# PiGateway2_2.net
KiCad netlist of a schematic drawn in EAGLE
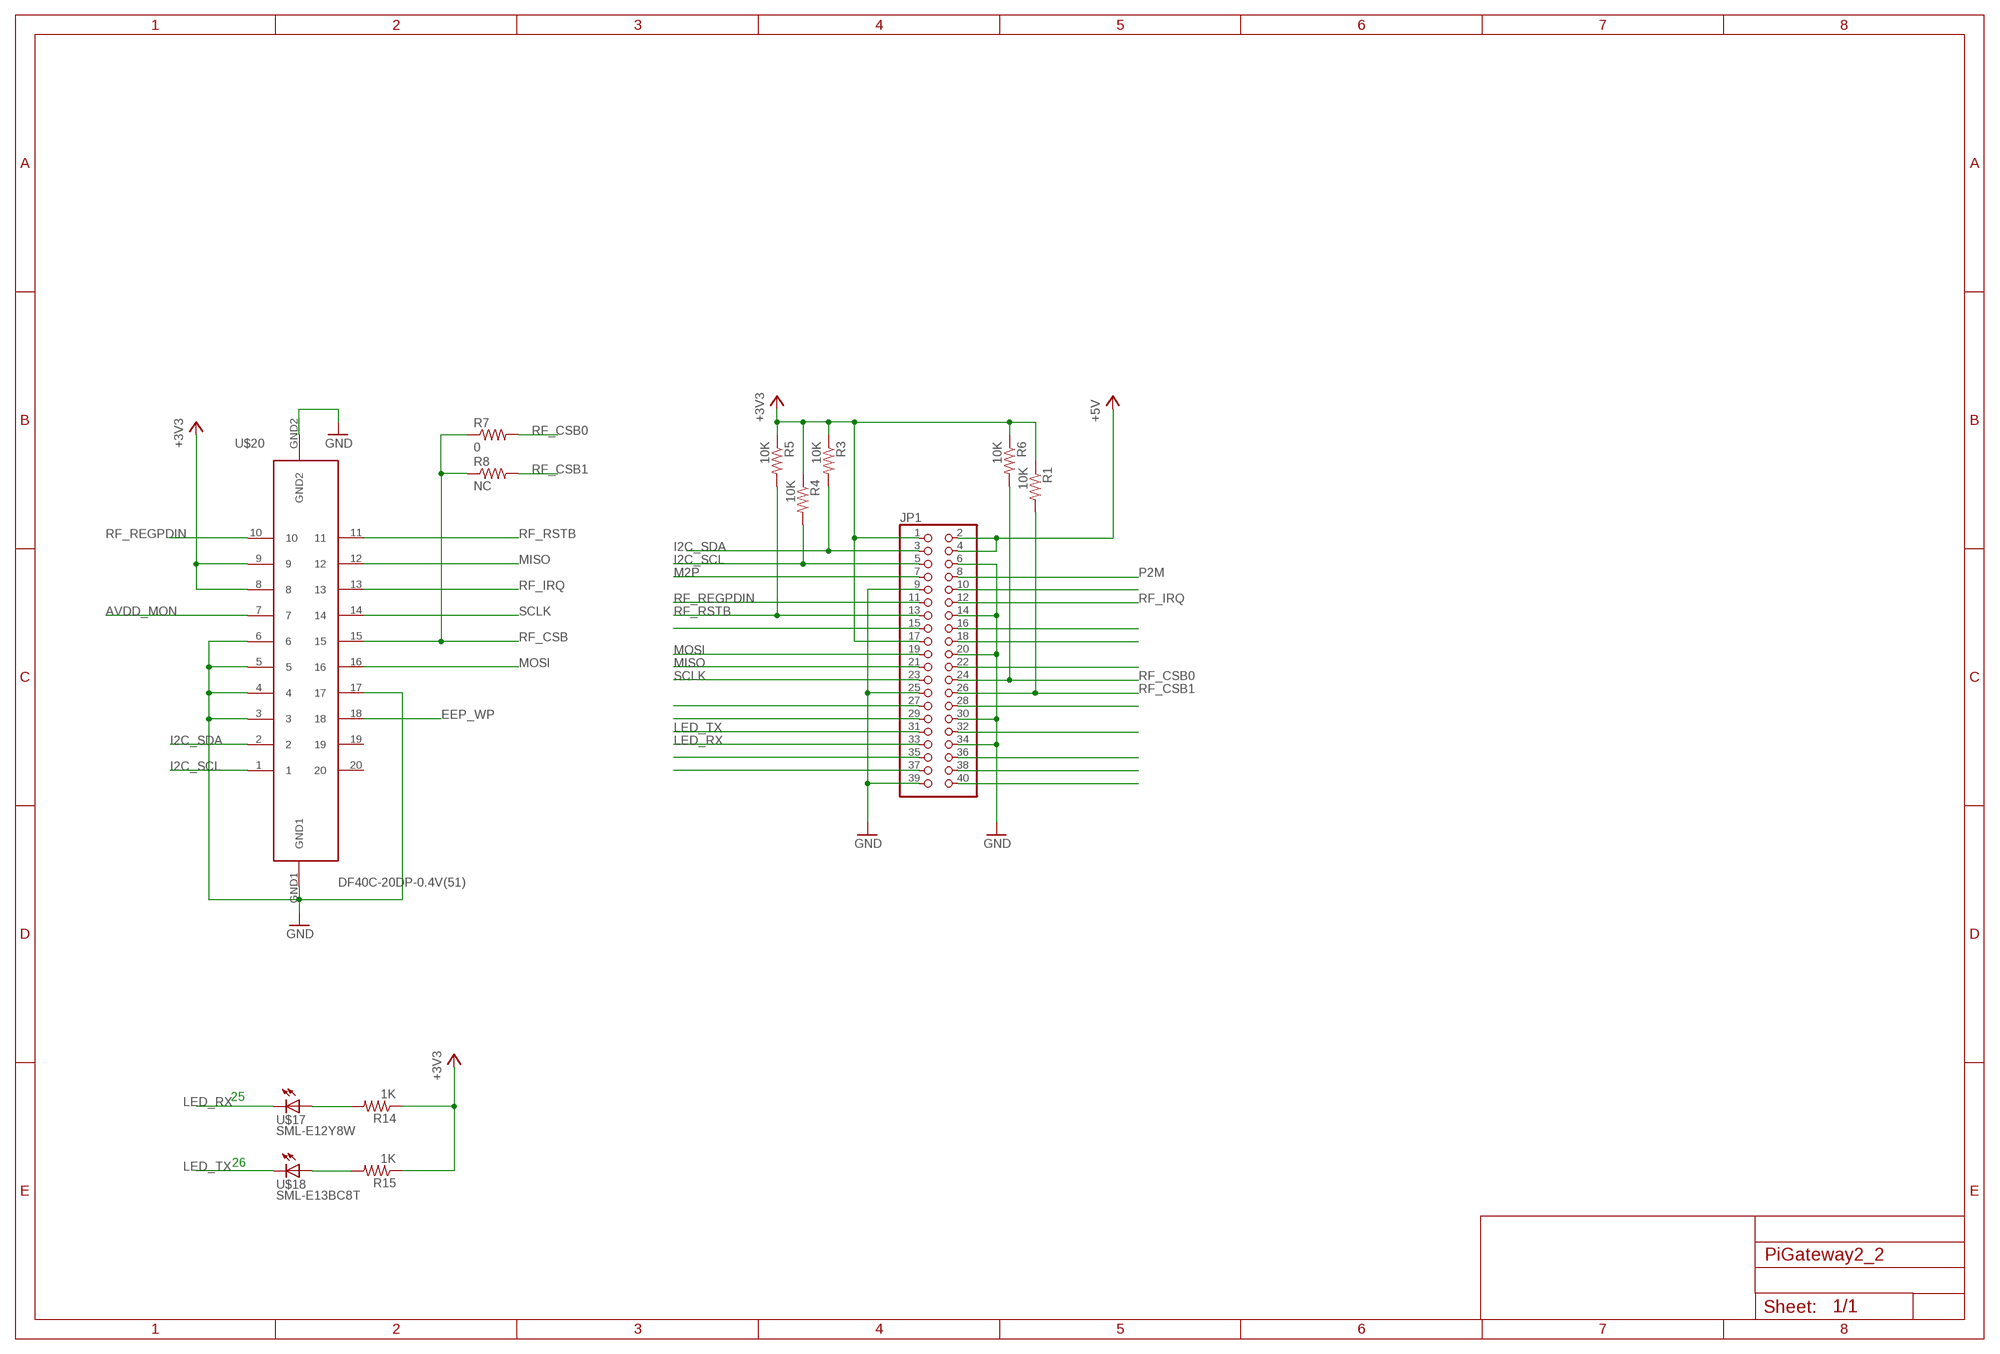
[diagram p0: schematic, sheet 1]

(export (version "E")
  (design (tool "Eeschema 10.0.6"))
  (components
    (comp (ref "JP1")
      (value "PINHD-2X20")
      (footprint "eagle-import:2X20")
      (libsource (lib "eagle-import") (part "PINHD-2X20"))
    )
    (comp (ref "R1")
      (value "10K")
      (footprint "eagle-import:R0402")
      (libsource (lib "eagle-import") (part "R-US_R0402"))
    )
    (comp (ref "R3")
      (value "10K")
      (footprint "eagle-import:R0402")
      (libsource (lib "eagle-import") (part "R-US_R0402"))
    )
    (comp (ref "R4")
      (value "10K")
      (footprint "eagle-import:R0402")
      (libsource (lib "eagle-import") (part "R-US_R0402"))
    )
    (comp (ref "R5")
      (value "10K")
      (footprint "eagle-import:R0402")
      (libsource (lib "eagle-import") (part "R-US_R0402"))
    )
    (comp (ref "R6")
      (value "10K")
      (footprint "eagle-import:R0402")
      (libsource (lib "eagle-import") (part "R-US_R0402"))
    )
    (comp (ref "R7")
      (value "0")
      (footprint "eagle-import:R0402")
      (libsource (lib "eagle-import") (part "R-US_R0402"))
    )
    (comp (ref "R8")
      (value "NC")
      (footprint "eagle-import:R0402")
      (libsource (lib "eagle-import") (part "R-US_R0402"))
    )
    (comp (ref "R14")
      (value "1K")
      (footprint "eagle-import:R0402")
      (libsource (lib "eagle-import") (part "R-US_R0402"))
    )
    (comp (ref "R15")
      (value "1K")
      (footprint "eagle-import:R0402")
      (libsource (lib "eagle-import") (part "R-US_R0402"))
    )
    (comp (ref "U$17")
      (value "SML-E12Y8W")
      (footprint "eagle-import:SML-E1X")
      (libsource (lib "eagle-import") (part "SML-E1X"))
    )
    (comp (ref "U$18")
      (value "SML-E13BC8T")
      (footprint "eagle-import:SML-E1X")
      (libsource (lib "eagle-import") (part "SML-E1X"))
    )
    (comp (ref "U$20")
      (value "DF40C-20DP-0.4V(51)")
      (footprint "eagle-import:BP3596A")
      (libsource (lib "eagle-import") (part "BP3596A"))
    )
  )
  (nets
    (net (code "1") (name "+3V3") (class "Default")
      (node (ref "JP1") (pin "1") (pinfunction "1_1") (pintype "passive"))
      (node (ref "JP1") (pin "17") (pinfunction "17_17") (pintype "passive"))
      (node (ref "R1") (pin "1") (pinfunction "1_1") (pintype "passive"))
      (node (ref "R14") (pin "1") (pinfunction "1_1") (pintype "passive"))
      (node (ref "R15") (pin "1") (pinfunction "1_1") (pintype "passive"))
      (node (ref "R3") (pin "1") (pinfunction "1_1") (pintype "passive"))
      (node (ref "R4") (pin "1") (pinfunction "1_1") (pintype "passive"))
      (node (ref "R5") (pin "1") (pinfunction "1_1") (pintype "passive"))
      (node (ref "R6") (pin "1") (pinfunction "1_1") (pintype "passive"))
      (node (ref "U$20") (pin "8") (pinfunction "8_8") (pintype "bidirectional"))
      (node (ref "U$20") (pin "9") (pinfunction "9_9") (pintype "bidirectional"))
    )
    (net (code "2") (name "+5V") (class "Default")
      (node (ref "JP1") (pin "2") (pinfunction "2_2") (pintype "passive"))
      (node (ref "JP1") (pin "4") (pinfunction "4_4") (pintype "passive"))
    )
    (net (code "3") (name "/AVDD_MON") (class "Default")
      (node (ref "U$20") (pin "7") (pinfunction "7_7") (pintype "bidirectional"))
    )
    (net (code "4") (name "/EEP_WP") (class "Default")
      (node (ref "U$20") (pin "18") (pinfunction "18_18") (pintype "bidirectional"))
    )
    (net (code "5") (name "/I2C_SCL") (class "Default")
      (node (ref "JP1") (pin "5") (pinfunction "5_5") (pintype "passive"))
      (node (ref "R4") (pin "2") (pinfunction "2_2") (pintype "passive"))
      (node (ref "U$20") (pin "1") (pinfunction "1_1") (pintype "bidirectional"))
    )
    (net (code "6") (name "/I2C_SDA") (class "Default")
      (node (ref "JP1") (pin "3") (pinfunction "3_3") (pintype "passive"))
      (node (ref "R3") (pin "2") (pinfunction "2_2") (pintype "passive"))
      (node (ref "U$20") (pin "2") (pinfunction "2_2") (pintype "bidirectional"))
    )
    (net (code "7") (name "/LED_RX") (class "Default")
      (node (ref "JP1") (pin "33") (pinfunction "33_33") (pintype "passive"))
      (node (ref "U$17") (pin "C") (pinfunction "C_C") (pintype "passive"))
    )
    (net (code "8") (name "/LED_TX") (class "Default")
      (node (ref "JP1") (pin "31") (pinfunction "31_31") (pintype "passive"))
      (node (ref "U$18") (pin "C") (pinfunction "C_C") (pintype "passive"))
    )
    (net (code "9") (name "/M2P") (class "Default")
      (node (ref "JP1") (pin "7") (pinfunction "7_7") (pintype "passive"))
    )
    (net (code "10") (name "/MISO") (class "Default")
      (node (ref "JP1") (pin "21") (pinfunction "21_21") (pintype "passive"))
      (node (ref "U$20") (pin "12") (pinfunction "12_12") (pintype "bidirectional"))
    )
    (net (code "11") (name "/MOSI") (class "Default")
      (node (ref "JP1") (pin "19") (pinfunction "19_19") (pintype "passive"))
      (node (ref "U$20") (pin "16") (pinfunction "16_16") (pintype "bidirectional"))
    )
    (net (code "12") (name "/P2M") (class "Default")
      (node (ref "JP1") (pin "8") (pinfunction "8_8") (pintype "passive"))
    )
    (net (code "13") (name "/RF_CSB") (class "Default")
      (node (ref "R7") (pin "1") (pinfunction "1_1") (pintype "passive"))
      (node (ref "R8") (pin "1") (pinfunction "1_1") (pintype "passive"))
      (node (ref "U$20") (pin "15") (pinfunction "15_15") (pintype "bidirectional"))
    )
    (net (code "14") (name "/RF_CSB0") (class "Default")
      (node (ref "JP1") (pin "24") (pinfunction "24_24") (pintype "passive"))
      (node (ref "R6") (pin "2") (pinfunction "2_2") (pintype "passive"))
      (node (ref "R7") (pin "2") (pinfunction "2_2") (pintype "passive"))
    )
    (net (code "15") (name "/RF_CSB1") (class "Default")
      (node (ref "JP1") (pin "26") (pinfunction "26_26") (pintype "passive"))
      (node (ref "R1") (pin "2") (pinfunction "2_2") (pintype "passive"))
      (node (ref "R8") (pin "2") (pinfunction "2_2") (pintype "passive"))
    )
    (net (code "16") (name "/RF_IRQ") (class "Default")
      (node (ref "JP1") (pin "12") (pinfunction "12_12") (pintype "passive"))
      (node (ref "U$20") (pin "13") (pinfunction "13_13") (pintype "bidirectional"))
    )
    (net (code "17") (name "/RF_REGPDIN") (class "Default")
      (node (ref "JP1") (pin "11") (pinfunction "11_11") (pintype "passive"))
      (node (ref "U$20") (pin "10") (pinfunction "10_10") (pintype "bidirectional"))
    )
    (net (code "18") (name "/RF_RSTB") (class "Default")
      (node (ref "JP1") (pin "13") (pinfunction "13_13") (pintype "passive"))
      (node (ref "R5") (pin "2") (pinfunction "2_2") (pintype "passive"))
      (node (ref "U$20") (pin "11") (pinfunction "11_11") (pintype "bidirectional"))
    )
    (net (code "19") (name "/SCLK") (class "Default")
      (node (ref "JP1") (pin "23") (pinfunction "23_23") (pintype "passive"))
      (node (ref "U$20") (pin "14") (pinfunction "14_14") (pintype "bidirectional"))
    )
    (net (code "20") (name "GND") (class "Default")
      (node (ref "JP1") (pin "14") (pinfunction "14_14") (pintype "passive"))
      (node (ref "JP1") (pin "20") (pinfunction "20_20") (pintype "passive"))
      (node (ref "JP1") (pin "25") (pinfunction "25_25") (pintype "passive"))
      (node (ref "JP1") (pin "30") (pinfunction "30_30") (pintype "passive"))
      (node (ref "JP1") (pin "34") (pinfunction "34_34") (pintype "passive"))
      (node (ref "JP1") (pin "39") (pinfunction "39_39") (pintype "passive"))
      (node (ref "JP1") (pin "6") (pinfunction "6_6") (pintype "passive"))
      (node (ref "JP1") (pin "9") (pinfunction "9_9") (pintype "passive"))
      (node (ref "U$20") (pin "17") (pinfunction "17_17") (pintype "bidirectional"))
      (node (ref "U$20") (pin "3") (pinfunction "3_3") (pintype "bidirectional"))
      (node (ref "U$20") (pin "4") (pinfunction "4_4") (pintype "bidirectional"))
      (node (ref "U$20") (pin "5") (pinfunction "5_5") (pintype "bidirectional"))
      (node (ref "U$20") (pin "6") (pinfunction "6_6") (pintype "bidirectional"))
      (node (ref "U$20") (pin "GND1") (pinfunction "GND1_GND1") (pintype "bidirectional"))
      (node (ref "U$20") (pin "GND2") (pinfunction "GND2_GND2") (pintype "bidirectional"))
    )
    (net (code "21") (name "Net-(R14-Pad2)") (class "Default")
      (node (ref "R14") (pin "2") (pinfunction "2_2") (pintype "passive"))
      (node (ref "U$17") (pin "A") (pinfunction "A_A") (pintype "passive"))
    )
    (net (code "22") (name "Net-(R15-Pad2)") (class "Default")
      (node (ref "R15") (pin "2") (pinfunction "2_2") (pintype "passive"))
      (node (ref "U$18") (pin "A") (pinfunction "A_A") (pintype "passive"))
    )
    (net (code "23") (name "unconnected-(JP1-Pad10)") (class "Default")
      (node (ref "JP1") (pin "10") (pinfunction "10_10") (pintype "passive"))
    )
    (net (code "24") (name "unconnected-(JP1-Pad15)") (class "Default")
      (node (ref "JP1") (pin "15") (pinfunction "15_15") (pintype "passive"))
    )
    (net (code "25") (name "unconnected-(JP1-Pad16)") (class "Default")
      (node (ref "JP1") (pin "16") (pinfunction "16_16") (pintype "passive"))
    )
    (net (code "26") (name "unconnected-(JP1-Pad18)") (class "Default")
      (node (ref "JP1") (pin "18") (pinfunction "18_18") (pintype "passive"))
    )
    (net (code "27") (name "unconnected-(JP1-Pad22)") (class "Default")
      (node (ref "JP1") (pin "22") (pinfunction "22_22") (pintype "passive"))
    )
    (net (code "28") (name "unconnected-(JP1-Pad27)") (class "Default")
      (node (ref "JP1") (pin "27") (pinfunction "27_27") (pintype "passive"))
    )
    (net (code "29") (name "unconnected-(JP1-Pad28)") (class "Default")
      (node (ref "JP1") (pin "28") (pinfunction "28_28") (pintype "passive"))
    )
    (net (code "30") (name "unconnected-(JP1-Pad29)") (class "Default")
      (node (ref "JP1") (pin "29") (pinfunction "29_29") (pintype "passive"))
    )
    (net (code "31") (name "unconnected-(JP1-Pad32)") (class "Default")
      (node (ref "JP1") (pin "32") (pinfunction "32_32") (pintype "passive"))
    )
    (net (code "32") (name "unconnected-(JP1-Pad35)") (class "Default")
      (node (ref "JP1") (pin "35") (pinfunction "35_35") (pintype "passive"))
    )
    (net (code "33") (name "unconnected-(JP1-Pad36)") (class "Default")
      (node (ref "JP1") (pin "36") (pinfunction "36_36") (pintype "passive"))
    )
    (net (code "34") (name "unconnected-(JP1-Pad37)") (class "Default")
      (node (ref "JP1") (pin "37") (pinfunction "37_37") (pintype "passive"))
    )
    (net (code "35") (name "unconnected-(JP1-Pad38)") (class "Default")
      (node (ref "JP1") (pin "38") (pinfunction "38_38") (pintype "passive"))
    )
    (net (code "36") (name "unconnected-(JP1-Pad40)") (class "Default")
      (node (ref "JP1") (pin "40") (pinfunction "40_40") (pintype "passive"))
    )
    (net (code "37") (name "unconnected-(U$20-Pad19)") (class "Default")
      (node (ref "U$20") (pin "19") (pinfunction "19_19") (pintype "bidirectional"))
    )
    (net (code "38") (name "unconnected-(U$20-Pad20)") (class "Default")
      (node (ref "U$20") (pin "20") (pinfunction "20_20") (pintype "bidirectional"))
    )
  )
)
